# 3732_connectors.net
KiCad netlist of a schematic drawn in Altium Designer
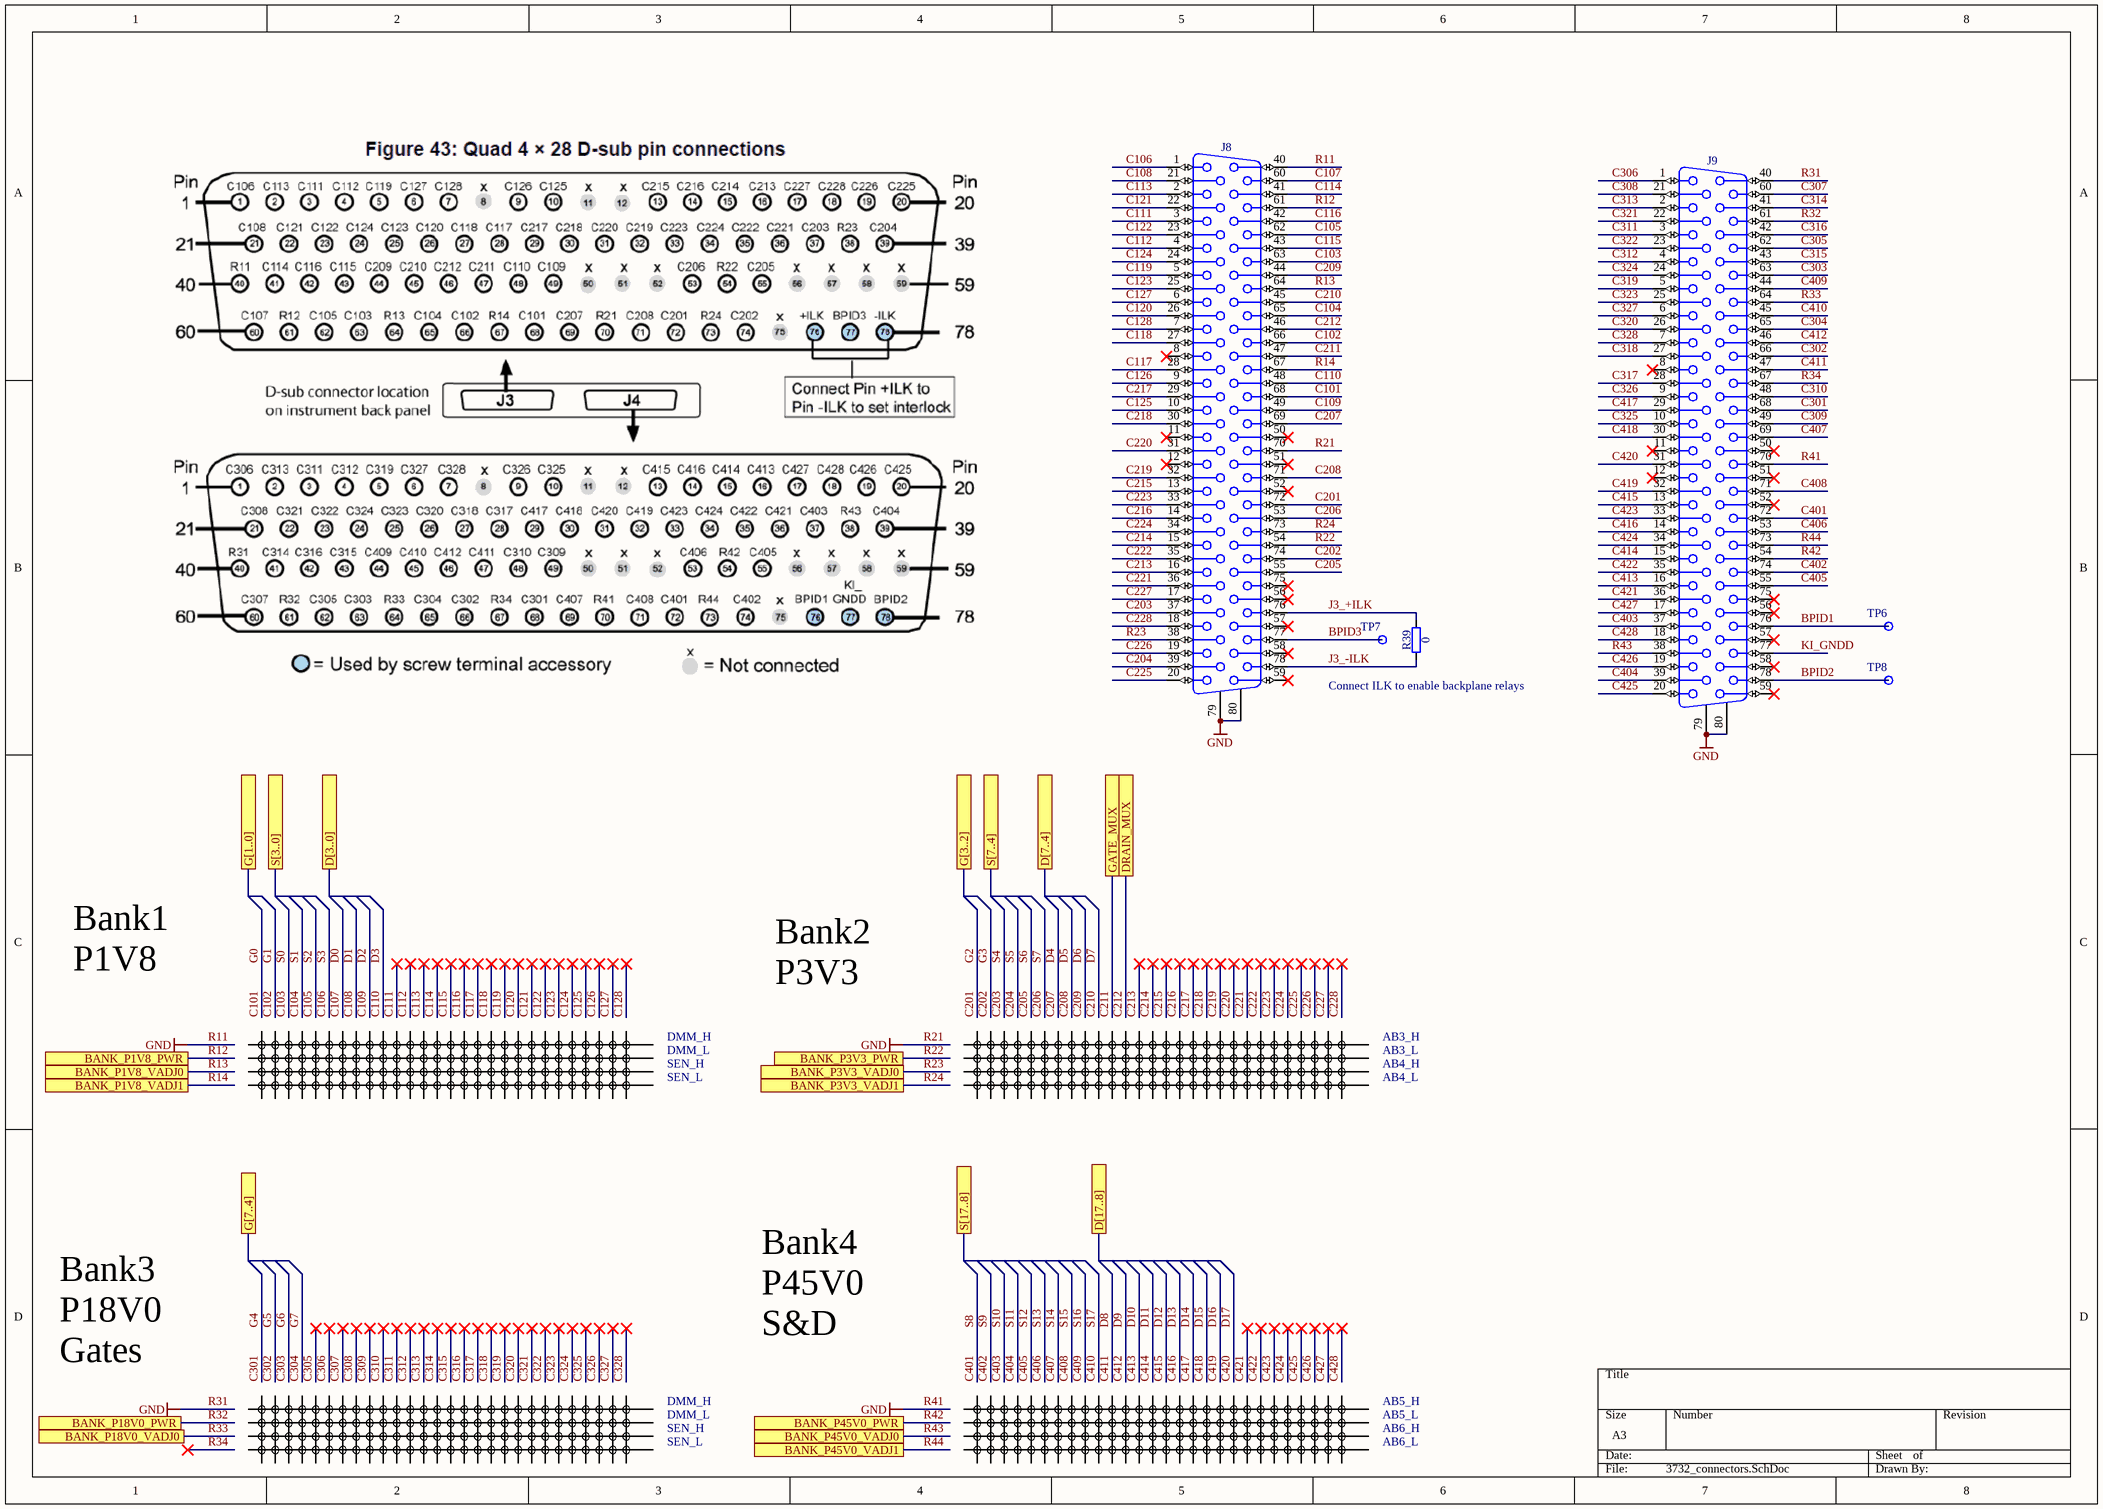
[diagram p0: 3732_connectors.SchDoc]

(export (version "E")
  (design (tool "Eeschema 10.0.6"))
  (components
    (comp (ref "J8")
      (value "D-Sub 78F")
      (footprint "HARTING_09 56 551 7513")
      (description "Connector D-sub 78 Female")
      (fields
        (field (name "PART NUMBER") "HARTING_09 56 551 7513")
        (field (name "MANUFACTURER") "HARTING")
        (field (name "AUTHOR") "CERN DEM JLC")
      )
      (libsource (lib "Connectors") (part "Connector D-sub 78 Female"))
    )
    (comp (ref "J9")
      (value "D-Sub 78F")
      (footprint "HARTING_09 56 551 7513")
      (description "Connector D-sub 78 Female")
      (fields
        (field (name "PART NUMBER") "HARTING_09 56 551 7513")
        (field (name "MANUFACTURER") "HARTING")
        (field (name "AUTHOR") "CERN DEM JLC")
      )
      (libsource (lib "Connectors") (part "Connector D-sub 78 Female"))
    )
    (comp (ref "R39")
      (value "0")
      (footprint "RESC1005X40N")
      (description "Resistor")
      (fields
        (field (name "PART NUMBER") "R0402_0R_JUMPER")
        (field (name "MANUFACTURER") "GENERIC")
        (field (name "AUTHOR") "CERN DEM JLC")
      )
      (libsource (lib "Resistors") (part "Resistor"))
    )
    (comp (ref "TP6")
      (value "Test Point")
      (footprint "TPS127")
      (fields (field (name "PART NUMBER") "SMD_PAD_1.27X1.27MM") (field (name "AUTHOR") "CERN DEM JLC"))
      (libsource (lib "Eletro-mechanical") (part "Test Point"))
    )
    (comp (ref "TP7")
      (value "Test Point")
      (footprint "TPS127")
      (fields (field (name "PART NUMBER") "SMD_PAD_1.27X1.27MM") (field (name "AUTHOR") "CERN DEM JLC"))
      (libsource (lib "Eletro-mechanical") (part "Test Point"))
    )
    (comp (ref "TP8")
      (value "Test Point")
      (footprint "TPS127")
      (fields (field (name "PART NUMBER") "SMD_PAD_1.27X1.27MM") (field (name "AUTHOR") "CERN DEM JLC"))
      (libsource (lib "Eletro-mechanical") (part "Test Point"))
    )
  )
  (nets
    (net (code "1") (name "/BPID1") (class "Default")
      (node (ref "J9") (pin "76") (pinfunction "76_76") (pintype "bidirectional"))
      (node (ref "TP6") (pin "1") (pinfunction "1_1") (pintype "bidirectional"))
    )
    (net (code "2") (name "/BPID2") (class "Default")
      (node (ref "J9") (pin "78") (pinfunction "78_78") (pintype "bidirectional"))
      (node (ref "TP8") (pin "1") (pinfunction "1_1") (pintype "bidirectional"))
    )
    (net (code "3") (name "/BPID3") (class "Default")
      (node (ref "J8") (pin "77") (pinfunction "77_77") (pintype "bidirectional"))
      (node (ref "TP7") (pin "1") (pinfunction "1_1") (pintype "bidirectional"))
    )
    (net (code "4") (name "/C111") (class "Default")
      (node (ref "J8") (pin "3") (pinfunction "3_3") (pintype "bidirectional+no_connect"))
    )
    (net (code "5") (name "/C112") (class "Default")
      (node (ref "J8") (pin "4") (pinfunction "4_4") (pintype "bidirectional+no_connect"))
    )
    (net (code "6") (name "/C113") (class "Default")
      (node (ref "J8") (pin "2") (pinfunction "2_2") (pintype "bidirectional+no_connect"))
    )
    (net (code "7") (name "/C114") (class "Default")
      (node (ref "J8") (pin "41") (pinfunction "41_41") (pintype "bidirectional+no_connect"))
    )
    (net (code "8") (name "/C115") (class "Default")
      (node (ref "J8") (pin "43") (pinfunction "43_43") (pintype "bidirectional+no_connect"))
    )
    (net (code "9") (name "/C116") (class "Default")
      (node (ref "J8") (pin "42") (pinfunction "42_42") (pintype "bidirectional+no_connect"))
    )
    (net (code "10") (name "/C117") (class "Default")
      (node (ref "J8") (pin "28") (pinfunction "28_28") (pintype "bidirectional+no_connect"))
    )
    (net (code "11") (name "/C118") (class "Default")
      (node (ref "J8") (pin "27") (pinfunction "27_27") (pintype "bidirectional+no_connect"))
    )
    (net (code "12") (name "/C119") (class "Default")
      (node (ref "J8") (pin "5") (pinfunction "5_5") (pintype "bidirectional+no_connect"))
    )
    (net (code "13") (name "/C120") (class "Default")
      (node (ref "J8") (pin "26") (pinfunction "26_26") (pintype "bidirectional+no_connect"))
    )
    (net (code "14") (name "/C121") (class "Default")
      (node (ref "J8") (pin "22") (pinfunction "22_22") (pintype "bidirectional+no_connect"))
    )
    (net (code "15") (name "/C122") (class "Default")
      (node (ref "J8") (pin "23") (pinfunction "23_23") (pintype "bidirectional+no_connect"))
    )
    (net (code "16") (name "/C123") (class "Default")
      (node (ref "J8") (pin "25") (pinfunction "25_25") (pintype "bidirectional+no_connect"))
    )
    (net (code "17") (name "/C124") (class "Default")
      (node (ref "J8") (pin "24") (pinfunction "24_24") (pintype "bidirectional+no_connect"))
    )
    (net (code "18") (name "/C125") (class "Default")
      (node (ref "J8") (pin "10") (pinfunction "10_10") (pintype "bidirectional+no_connect"))
    )
    (net (code "19") (name "/C126") (class "Default")
      (node (ref "J8") (pin "9") (pinfunction "9_9") (pintype "bidirectional+no_connect"))
    )
    (net (code "20") (name "/C127") (class "Default")
      (node (ref "J8") (pin "6") (pinfunction "6_6") (pintype "bidirectional+no_connect"))
    )
    (net (code "21") (name "/C128") (class "Default")
      (node (ref "J8") (pin "7") (pinfunction "7_7") (pintype "bidirectional+no_connect"))
    )
    (net (code "22") (name "/C211") (class "Default")
      (node (ref "J8") (pin "47") (pinfunction "47_47") (pintype "bidirectional"))
    )
    (net (code "23") (name "/C212") (class "Default")
      (node (ref "J8") (pin "46") (pinfunction "46_46") (pintype "bidirectional"))
    )
    (net (code "24") (name "/C213") (class "Default")
      (node (ref "J8") (pin "16") (pinfunction "16_16") (pintype "bidirectional"))
    )
    (net (code "25") (name "/C214") (class "Default")
      (node (ref "J8") (pin "15") (pinfunction "15_15") (pintype "bidirectional"))
    )
    (net (code "26") (name "/C215") (class "Default")
      (node (ref "J8") (pin "13") (pinfunction "13_13") (pintype "bidirectional"))
    )
    (net (code "27") (name "/C216") (class "Default")
      (node (ref "J8") (pin "14") (pinfunction "14_14") (pintype "bidirectional"))
    )
    (net (code "28") (name "/C217") (class "Default")
      (node (ref "J8") (pin "29") (pinfunction "29_29") (pintype "bidirectional"))
    )
    (net (code "29") (name "/C218") (class "Default")
      (node (ref "J8") (pin "30") (pinfunction "30_30") (pintype "bidirectional+no_connect"))
    )
    (net (code "30") (name "/C219") (class "Default")
      (node (ref "J8") (pin "32") (pinfunction "32_32") (pintype "bidirectional+no_connect"))
    )
    (net (code "31") (name "/C220") (class "Default")
      (node (ref "J8") (pin "31") (pinfunction "31_31") (pintype "bidirectional+no_connect"))
    )
    (net (code "32") (name "/C221") (class "Default")
      (node (ref "J8") (pin "36") (pinfunction "36_36") (pintype "bidirectional+no_connect"))
    )
    (net (code "33") (name "/C222") (class "Default")
      (node (ref "J8") (pin "35") (pinfunction "35_35") (pintype "bidirectional+no_connect"))
    )
    (net (code "34") (name "/C223") (class "Default")
      (node (ref "J8") (pin "33") (pinfunction "33_33") (pintype "bidirectional+no_connect"))
    )
    (net (code "35") (name "/C224") (class "Default")
      (node (ref "J8") (pin "34") (pinfunction "34_34") (pintype "bidirectional+no_connect"))
    )
    (net (code "36") (name "/C225") (class "Default")
      (node (ref "J8") (pin "20") (pinfunction "20_20") (pintype "bidirectional+no_connect"))
    )
    (net (code "37") (name "/C226") (class "Default")
      (node (ref "J8") (pin "19") (pinfunction "19_19") (pintype "bidirectional+no_connect"))
    )
    (net (code "38") (name "/C227") (class "Default")
      (node (ref "J8") (pin "17") (pinfunction "17_17") (pintype "bidirectional+no_connect"))
    )
    (net (code "39") (name "/C228") (class "Default")
      (node (ref "J8") (pin "18") (pinfunction "18_18") (pintype "bidirectional+no_connect"))
    )
    (net (code "40") (name "/C305") (class "Default")
      (node (ref "J9") (pin "62") (pinfunction "62_62") (pintype "bidirectional+no_connect"))
    )
    (net (code "41") (name "/C306") (class "Default")
      (node (ref "J9") (pin "1") (pinfunction "1_1") (pintype "bidirectional+no_connect"))
    )
    (net (code "42") (name "/C307") (class "Default")
      (node (ref "J9") (pin "60") (pinfunction "60_60") (pintype "bidirectional+no_connect"))
    )
    (net (code "43") (name "/C308") (class "Default")
      (node (ref "J9") (pin "21") (pinfunction "21_21") (pintype "bidirectional+no_connect"))
    )
    (net (code "44") (name "/C309") (class "Default")
      (node (ref "J9") (pin "49") (pinfunction "49_49") (pintype "bidirectional+no_connect"))
    )
    (net (code "45") (name "/C310") (class "Default")
      (node (ref "J9") (pin "48") (pinfunction "48_48") (pintype "bidirectional+no_connect"))
    )
    (net (code "46") (name "/C311") (class "Default")
      (node (ref "J9") (pin "3") (pinfunction "3_3") (pintype "bidirectional+no_connect"))
    )
    (net (code "47") (name "/C312") (class "Default")
      (node (ref "J9") (pin "4") (pinfunction "4_4") (pintype "bidirectional+no_connect"))
    )
    (net (code "48") (name "/C313") (class "Default")
      (node (ref "J9") (pin "2") (pinfunction "2_2") (pintype "bidirectional+no_connect"))
    )
    (net (code "49") (name "/C314") (class "Default")
      (node (ref "J9") (pin "41") (pinfunction "41_41") (pintype "bidirectional+no_connect"))
    )
    (net (code "50") (name "/C315") (class "Default")
      (node (ref "J9") (pin "43") (pinfunction "43_43") (pintype "bidirectional+no_connect"))
    )
    (net (code "51") (name "/C316") (class "Default")
      (node (ref "J9") (pin "42") (pinfunction "42_42") (pintype "bidirectional+no_connect"))
    )
    (net (code "52") (name "/C317") (class "Default")
      (node (ref "J9") (pin "28") (pinfunction "28_28") (pintype "bidirectional+no_connect"))
    )
    (net (code "53") (name "/C318") (class "Default")
      (node (ref "J9") (pin "27") (pinfunction "27_27") (pintype "bidirectional+no_connect"))
    )
    (net (code "54") (name "/C319") (class "Default")
      (node (ref "J9") (pin "5") (pinfunction "5_5") (pintype "bidirectional+no_connect"))
    )
    (net (code "55") (name "/C320") (class "Default")
      (node (ref "J9") (pin "26") (pinfunction "26_26") (pintype "bidirectional+no_connect"))
    )
    (net (code "56") (name "/C321") (class "Default")
      (node (ref "J9") (pin "22") (pinfunction "22_22") (pintype "bidirectional+no_connect"))
    )
    (net (code "57") (name "/C322") (class "Default")
      (node (ref "J9") (pin "23") (pinfunction "23_23") (pintype "bidirectional+no_connect"))
    )
    (net (code "58") (name "/C323") (class "Default")
      (node (ref "J9") (pin "25") (pinfunction "25_25") (pintype "bidirectional+no_connect"))
    )
    (net (code "59") (name "/C324") (class "Default")
      (node (ref "J9") (pin "24") (pinfunction "24_24") (pintype "bidirectional+no_connect"))
    )
    (net (code "60") (name "/C325") (class "Default")
      (node (ref "J9") (pin "10") (pinfunction "10_10") (pintype "bidirectional+no_connect"))
    )
    (net (code "61") (name "/C326") (class "Default")
      (node (ref "J9") (pin "9") (pinfunction "9_9") (pintype "bidirectional+no_connect"))
    )
    (net (code "62") (name "/C327") (class "Default")
      (node (ref "J9") (pin "6") (pinfunction "6_6") (pintype "bidirectional+no_connect"))
    )
    (net (code "63") (name "/C328") (class "Default")
      (node (ref "J9") (pin "7") (pinfunction "7_7") (pintype "bidirectional+no_connect"))
    )
    (net (code "64") (name "/C421") (class "Default")
      (node (ref "J9") (pin "36") (pinfunction "36_36") (pintype "bidirectional+no_connect"))
    )
    (net (code "65") (name "/C422") (class "Default")
      (node (ref "J9") (pin "35") (pinfunction "35_35") (pintype "bidirectional+no_connect"))
    )
    (net (code "66") (name "/C423") (class "Default")
      (node (ref "J9") (pin "33") (pinfunction "33_33") (pintype "bidirectional+no_connect"))
    )
    (net (code "67") (name "/C424") (class "Default")
      (node (ref "J9") (pin "34") (pinfunction "34_34") (pintype "bidirectional+no_connect"))
    )
    (net (code "68") (name "/C425") (class "Default")
      (node (ref "J9") (pin "20") (pinfunction "20_20") (pintype "bidirectional+no_connect"))
    )
    (net (code "69") (name "/C426") (class "Default")
      (node (ref "J9") (pin "19") (pinfunction "19_19") (pintype "bidirectional+no_connect"))
    )
    (net (code "70") (name "/C427") (class "Default")
      (node (ref "J9") (pin "17") (pinfunction "17_17") (pintype "bidirectional+no_connect"))
    )
    (net (code "71") (name "/C428") (class "Default")
      (node (ref "J9") (pin "18") (pinfunction "18_18") (pintype "bidirectional+no_connect"))
    )
    (net (code "72") (name "/D0") (class "Default")
      (node (ref "J8") (pin "60") (pinfunction "60_60") (pintype "bidirectional"))
    )
    (net (code "73") (name "/D1") (class "Default")
      (node (ref "J8") (pin "21") (pinfunction "21_21") (pintype "bidirectional"))
    )
    (net (code "74") (name "/D2") (class "Default")
      (node (ref "J8") (pin "49") (pinfunction "49_49") (pintype "bidirectional"))
    )
    (net (code "75") (name "/D3") (class "Default")
      (node (ref "J8") (pin "48") (pinfunction "48_48") (pintype "bidirectional"))
    )
    (net (code "76") (name "/D4") (class "Default")
      (node (ref "J8") (pin "69") (pinfunction "69_69") (pintype "bidirectional"))
    )
    (net (code "77") (name "/D5") (class "Default")
      (node (ref "J8") (pin "71") (pinfunction "71_71") (pintype "bidirectional"))
    )
    (net (code "78") (name "/D6") (class "Default")
      (node (ref "J8") (pin "44") (pinfunction "44_44") (pintype "bidirectional"))
    )
    (net (code "79") (name "/D7") (class "Default")
      (node (ref "J8") (pin "45") (pinfunction "45_45") (pintype "bidirectional"))
    )
    (net (code "80") (name "/D8") (class "Default")
      (node (ref "J9") (pin "47") (pinfunction "47_47") (pintype "bidirectional"))
    )
    (net (code "81") (name "/D9") (class "Default")
      (node (ref "J9") (pin "46") (pinfunction "46_46") (pintype "bidirectional"))
    )
    (net (code "82") (name "/D10") (class "Default")
      (node (ref "J9") (pin "16") (pinfunction "16_16") (pintype "bidirectional"))
    )
    (net (code "83") (name "/D11") (class "Default")
      (node (ref "J9") (pin "15") (pinfunction "15_15") (pintype "bidirectional"))
    )
    (net (code "84") (name "/D12") (class "Default")
      (node (ref "J9") (pin "13") (pinfunction "13_13") (pintype "bidirectional"))
    )
    (net (code "85") (name "/D13") (class "Default")
      (node (ref "J9") (pin "14") (pinfunction "14_14") (pintype "bidirectional"))
    )
    (net (code "86") (name "/D14") (class "Default")
      (node (ref "J9") (pin "29") (pinfunction "29_29") (pintype "bidirectional"))
    )
    (net (code "87") (name "/D15") (class "Default")
      (node (ref "J9") (pin "30") (pinfunction "30_30") (pintype "bidirectional"))
    )
    (net (code "88") (name "/D16") (class "Default")
      (node (ref "J9") (pin "32") (pinfunction "32_32") (pintype "bidirectional"))
    )
    (net (code "89") (name "/D17") (class "Default")
      (node (ref "J9") (pin "31") (pinfunction "31_31") (pintype "bidirectional"))
    )
    (net (code "93") (name "/G0") (class "Default")
      (node (ref "J8") (pin "68") (pinfunction "68_68") (pintype "bidirectional"))
    )
    (net (code "94") (name "/G1") (class "Default")
      (node (ref "J8") (pin "66") (pinfunction "66_66") (pintype "bidirectional"))
    )
    (net (code "95") (name "/G2") (class "Default")
      (node (ref "J8") (pin "72") (pinfunction "72_72") (pintype "bidirectional"))
    )
    (net (code "96") (name "/G3") (class "Default")
      (node (ref "J8") (pin "74") (pinfunction "74_74") (pintype "bidirectional"))
    )
    (net (code "97") (name "/G4") (class "Default")
      (node (ref "J9") (pin "68") (pinfunction "68_68") (pintype "bidirectional"))
    )
    (net (code "98") (name "/G5") (class "Default")
      (node (ref "J9") (pin "66") (pinfunction "66_66") (pintype "bidirectional"))
    )
    (net (code "99") (name "/G6") (class "Default")
      (node (ref "J9") (pin "63") (pinfunction "63_63") (pintype "bidirectional"))
    )
    (net (code "100") (name "/G7") (class "Default")
      (node (ref "J9") (pin "65") (pinfunction "65_65") (pintype "bidirectional"))
    )
    (net (code "104") (name "/J3_+ILK") (class "Default")
      (node (ref "J8") (pin "76") (pinfunction "76_76") (pintype "bidirectional"))
      (node (ref "R39") (pin "2") (pinfunction "2_2") (pintype "passive"))
    )
    (net (code "105") (name "/J3_-ILK") (class "Default")
      (node (ref "J8") (pin "78") (pinfunction "78_78") (pintype "bidirectional"))
      (node (ref "R39") (pin "1") (pinfunction "1_1") (pintype "passive"))
    )
    (net (code "106") (name "/KI_GNDD") (class "Default")
      (node (ref "J9") (pin "77") (pinfunction "77_77") (pintype "bidirectional"))
    )
    (net (code "107") (name "/R12") (class "Default")
      (node (ref "J8") (pin "61") (pinfunction "61_61") (pintype "bidirectional"))
    )
    (net (code "108") (name "/R13") (class "Default")
      (node (ref "J8") (pin "64") (pinfunction "64_64") (pintype "bidirectional"))
    )
    (net (code "109") (name "/R14") (class "Default")
      (node (ref "J8") (pin "67") (pinfunction "67_67") (pintype "bidirectional"))
    )
    (net (code "110") (name "/R22") (class "Default")
      (node (ref "J8") (pin "54") (pinfunction "54_54") (pintype "bidirectional"))
    )
    (net (code "111") (name "/R23") (class "Default")
      (node (ref "J8") (pin "38") (pinfunction "38_38") (pintype "bidirectional"))
    )
    (net (code "112") (name "/R24") (class "Default")
      (node (ref "J8") (pin "73") (pinfunction "73_73") (pintype "bidirectional"))
    )
    (net (code "113") (name "/R32") (class "Default")
      (node (ref "J9") (pin "61") (pinfunction "61_61") (pintype "bidirectional"))
    )
    (net (code "114") (name "/R33") (class "Default")
      (node (ref "J9") (pin "64") (pinfunction "64_64") (pintype "bidirectional"))
    )
    (net (code "115") (name "/R34") (class "Default")
      (node (ref "J9") (pin "67") (pinfunction "67_67") (pintype "bidirectional+no_connect"))
    )
    (net (code "116") (name "/R42") (class "Default")
      (node (ref "J9") (pin "54") (pinfunction "54_54") (pintype "bidirectional"))
    )
    (net (code "117") (name "/R43") (class "Default")
      (node (ref "J9") (pin "38") (pinfunction "38_38") (pintype "bidirectional"))
    )
    (net (code "118") (name "/R44") (class "Default")
      (node (ref "J9") (pin "73") (pinfunction "73_73") (pintype "bidirectional"))
    )
    (net (code "119") (name "/S0") (class "Default")
      (node (ref "J8") (pin "63") (pinfunction "63_63") (pintype "bidirectional"))
    )
    (net (code "120") (name "/S1") (class "Default")
      (node (ref "J8") (pin "65") (pinfunction "65_65") (pintype "bidirectional"))
    )
    (net (code "121") (name "/S2") (class "Default")
      (node (ref "J8") (pin "62") (pinfunction "62_62") (pintype "bidirectional"))
    )
    (net (code "122") (name "/S3") (class "Default")
      (node (ref "J8") (pin "1") (pinfunction "1_1") (pintype "bidirectional"))
    )
    (net (code "123") (name "/S4") (class "Default")
      (node (ref "J8") (pin "37") (pinfunction "37_37") (pintype "bidirectional"))
    )
    (net (code "124") (name "/S5") (class "Default")
      (node (ref "J8") (pin "39") (pinfunction "39_39") (pintype "bidirectional"))
    )
    (net (code "125") (name "/S6") (class "Default")
      (node (ref "J8") (pin "55") (pinfunction "55_55") (pintype "bidirectional"))
    )
    (net (code "126") (name "/S7") (class "Default")
      (node (ref "J8") (pin "53") (pinfunction "53_53") (pintype "bidirectional"))
    )
    (net (code "127") (name "/S8") (class "Default")
      (node (ref "J9") (pin "72") (pinfunction "72_72") (pintype "bidirectional"))
    )
    (net (code "128") (name "/S9") (class "Default")
      (node (ref "J9") (pin "74") (pinfunction "74_74") (pintype "bidirectional"))
    )
    (net (code "129") (name "/S10") (class "Default")
      (node (ref "J9") (pin "37") (pinfunction "37_37") (pintype "bidirectional"))
    )
    (net (code "130") (name "/S11") (class "Default")
      (node (ref "J9") (pin "39") (pinfunction "39_39") (pintype "bidirectional"))
    )
    (net (code "131") (name "/S12") (class "Default")
      (node (ref "J9") (pin "55") (pinfunction "55_55") (pintype "bidirectional"))
    )
    (net (code "132") (name "/S13") (class "Default")
      (node (ref "J9") (pin "53") (pinfunction "53_53") (pintype "bidirectional"))
    )
    (net (code "133") (name "/S14") (class "Default")
      (node (ref "J9") (pin "69") (pinfunction "69_69") (pintype "bidirectional"))
    )
    (net (code "134") (name "/S15") (class "Default")
      (node (ref "J9") (pin "71") (pinfunction "71_71") (pintype "bidirectional"))
    )
    (net (code "135") (name "/S16") (class "Default")
      (node (ref "J9") (pin "44") (pinfunction "44_44") (pintype "bidirectional"))
    )
    (net (code "136") (name "/S17") (class "Default")
      (node (ref "J9") (pin "45") (pinfunction "45_45") (pintype "bidirectional"))
    )
    (net (code "140") (name "GND") (class "Default")
      (node (ref "J8") (pin "40") (pinfunction "40_40") (pintype "bidirectional"))
      (node (ref "J8") (pin "70") (pinfunction "70_70") (pintype "bidirectional"))
      (node (ref "J8") (pin "79") (pinfunction "79_79") (pintype "passive"))
      (node (ref "J8") (pin "80") (pinfunction "80_80") (pintype "passive"))
      (node (ref "J9") (pin "40") (pinfunction "40_40") (pintype "bidirectional"))
      (node (ref "J9") (pin "70") (pinfunction "70_70") (pintype "bidirectional"))
      (node (ref "J9") (pin "79") (pinfunction "79_79") (pintype "passive"))
      (node (ref "J9") (pin "80") (pinfunction "80_80") (pintype "passive"))
    )
    (net (code "141") (name "unconnected-(J8-Pad8)") (class "Default")
      (node (ref "J8") (pin "8") (pinfunction "8_8") (pintype "bidirectional+no_connect"))
    )
    (net (code "142") (name "unconnected-(J8-Pad11)") (class "Default")
      (node (ref "J8") (pin "11") (pinfunction "11_11") (pintype "bidirectional+no_connect"))
    )
    (net (code "143") (name "unconnected-(J8-Pad12)") (class "Default")
      (node (ref "J8") (pin "12") (pinfunction "12_12") (pintype "bidirectional+no_connect"))
    )
    (net (code "144") (name "unconnected-(J8-Pad50)") (class "Default")
      (node (ref "J8") (pin "50") (pinfunction "50_50") (pintype "bidirectional+no_connect"))
    )
    (net (code "145") (name "unconnected-(J8-Pad51)") (class "Default")
      (node (ref "J8") (pin "51") (pinfunction "51_51") (pintype "bidirectional+no_connect"))
    )
    (net (code "146") (name "unconnected-(J8-Pad52)") (class "Default")
      (node (ref "J8") (pin "52") (pinfunction "52_52") (pintype "bidirectional+no_connect"))
    )
    (net (code "147") (name "unconnected-(J8-Pad56)") (class "Default")
      (node (ref "J8") (pin "56") (pinfunction "56_56") (pintype "bidirectional+no_connect"))
    )
    (net (code "148") (name "unconnected-(J8-Pad57)") (class "Default")
      (node (ref "J8") (pin "57") (pinfunction "57_57") (pintype "bidirectional+no_connect"))
    )
    (net (code "149") (name "unconnected-(J8-Pad58)") (class "Default")
      (node (ref "J8") (pin "58") (pinfunction "58_58") (pintype "bidirectional+no_connect"))
    )
    (net (code "150") (name "unconnected-(J8-Pad59)") (class "Default")
      (node (ref "J8") (pin "59") (pinfunction "59_59") (pintype "bidirectional+no_connect"))
    )
    (net (code "151") (name "unconnected-(J8-Pad75)") (class "Default")
      (node (ref "J8") (pin "75") (pinfunction "75_75") (pintype "bidirectional+no_connect"))
    )
    (net (code "152") (name "unconnected-(J9-Pad8)") (class "Default")
      (node (ref "J9") (pin "8") (pinfunction "8_8") (pintype "bidirectional+no_connect"))
    )
    (net (code "153") (name "unconnected-(J9-Pad11)") (class "Default")
      (node (ref "J9") (pin "11") (pinfunction "11_11") (pintype "bidirectional+no_connect"))
    )
    (net (code "154") (name "unconnected-(J9-Pad12)") (class "Default")
      (node (ref "J9") (pin "12") (pinfunction "12_12") (pintype "bidirectional+no_connect"))
    )
    (net (code "155") (name "unconnected-(J9-Pad50)") (class "Default")
      (node (ref "J9") (pin "50") (pinfunction "50_50") (pintype "bidirectional+no_connect"))
    )
    (net (code "156") (name "unconnected-(J9-Pad51)") (class "Default")
      (node (ref "J9") (pin "51") (pinfunction "51_51") (pintype "bidirectional+no_connect"))
    )
    (net (code "157") (name "unconnected-(J9-Pad52)") (class "Default")
      (node (ref "J9") (pin "52") (pinfunction "52_52") (pintype "bidirectional+no_connect"))
    )
    (net (code "158") (name "unconnected-(J9-Pad56)") (class "Default")
      (node (ref "J9") (pin "56") (pinfunction "56_56") (pintype "bidirectional+no_connect"))
    )
    (net (code "159") (name "unconnected-(J9-Pad57)") (class "Default")
      (node (ref "J9") (pin "57") (pinfunction "57_57") (pintype "bidirectional+no_connect"))
    )
    (net (code "160") (name "unconnected-(J9-Pad58)") (class "Default")
      (node (ref "J9") (pin "58") (pinfunction "58_58") (pintype "bidirectional+no_connect"))
    )
    (net (code "161") (name "unconnected-(J9-Pad59)") (class "Default")
      (node (ref "J9") (pin "59") (pinfunction "59_59") (pintype "bidirectional+no_connect"))
    )
    (net (code "162") (name "unconnected-(J9-Pad75)") (class "Default")
      (node (ref "J9") (pin "75") (pinfunction "75_75") (pintype "bidirectional+no_connect"))
    )
  )
)
